# Fox_Sound_Light.net
KiCad netlist of a schematic drawn in EAGLE
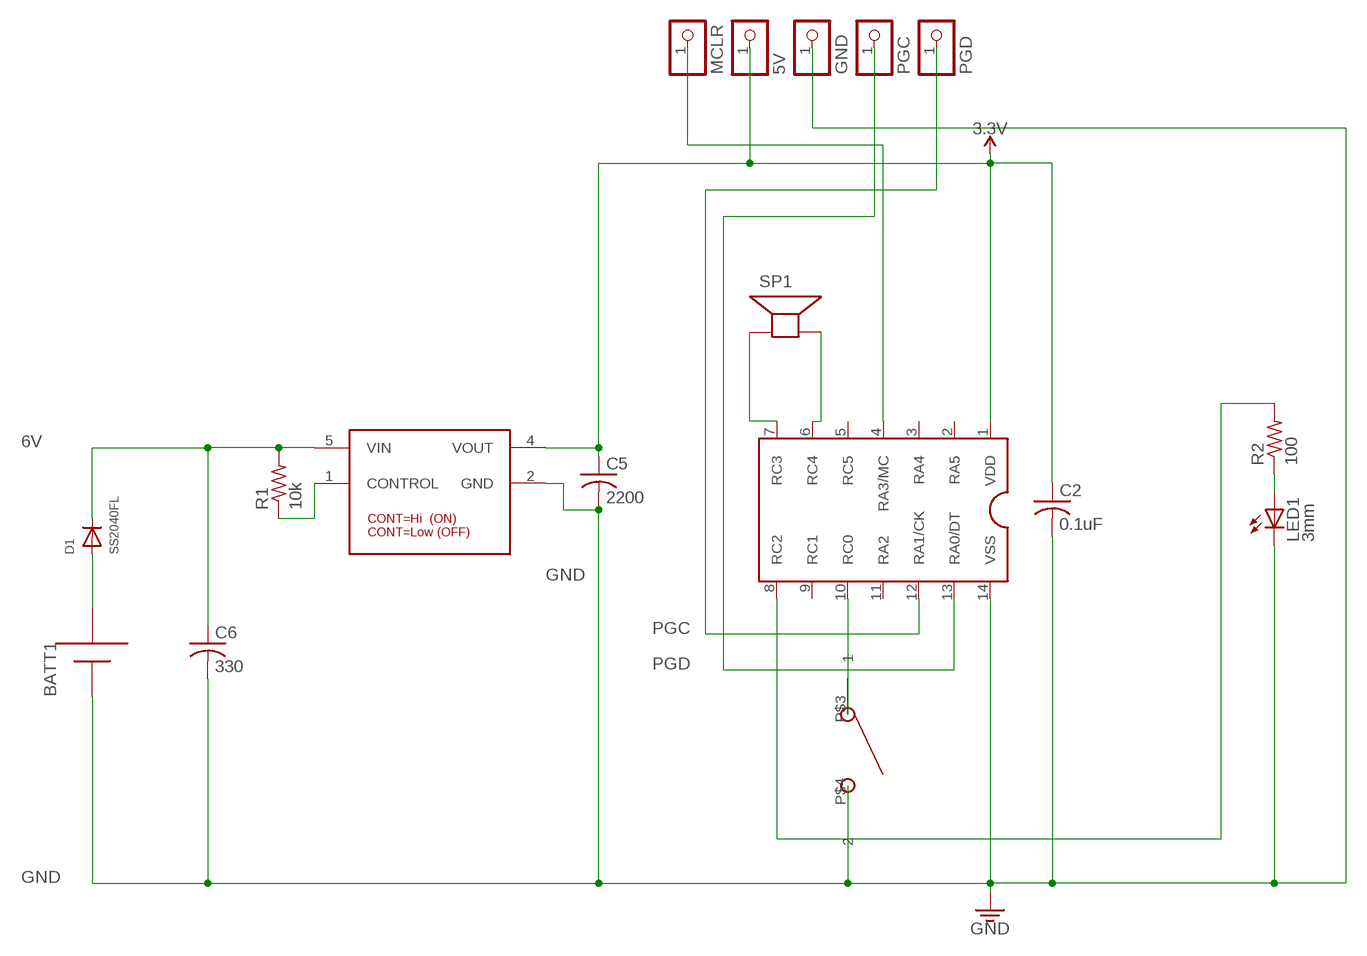
[diagram p0: schematic, sheet 1]

(export (version "E")
  (design (tool "Eeschema 10.0.6"))
  (components
    (comp (ref "BATT1")
      (value "AAA_CR2032X2")
      (footprint "eagle-import:CR2032X2")
      (libsource (lib "eagle-import") (part "AAA_CR2032X2"))
    )
    (comp (ref "C2")
      (value "0.1uF")
      (footprint "eagle-import:C0603")
      (libsource (lib "eagle-import") (part "mathrax_C-USC0603"))
    )
    (comp (ref "C5")
      (value "2200")
      (footprint "eagle-import:C3216")
      (libsource (lib "eagle-import") (part "C-USC3216"))
    )
    (comp (ref "C6")
      (value "330")
      (footprint "eagle-import:C0603")
      (libsource (lib "eagle-import") (part "mathrax_C-USC0603"))
    )
    (comp (ref "D1")
      (value "SS2040FL")
      (footprint "eagle-import:SOD-123FL")
      (libsource (lib "eagle-import") (part "DIODE_SOD-123FL"))
    )
    (comp (ref "JP1")
      (value "MCLR")
      (footprint "eagle-import:1X01-CLEANBIG")
      (libsource (lib "eagle-import") (part "PINHD-1X1CB"))
    )
    (comp (ref "JP2")
      (value "5V")
      (footprint "eagle-import:1X01-CLEANBIG")
      (libsource (lib "eagle-import") (part "PINHD-1X1CB"))
    )
    (comp (ref "JP3")
      (value "GND")
      (footprint "eagle-import:1X01-CLEANBIG")
      (libsource (lib "eagle-import") (part "PINHD-1X1CB"))
    )
    (comp (ref "JP4")
      (value "PGC")
      (footprint "eagle-import:1X01-CLEANBIG")
      (libsource (lib "eagle-import") (part "PINHD-1X1CB"))
    )
    (comp (ref "JP5")
      (value "PGD")
      (footprint "eagle-import:1X01-CLEANBIG")
      (libsource (lib "eagle-import") (part "PINHD-1X1CB"))
    )
    (comp (ref "LED1")
      (value "3mm")
      (footprint "eagle-import:LED3MM")
      (libsource (lib "eagle-import") (part "LED3MM"))
    )
    (comp (ref "NJM2884")
      (value "NJM2884")
      (footprint "eagle-import:NJM2884U1-33")
      (libsource (lib "eagle-import") (part "I-10673_NJM2884U1-33"))
    )
    (comp (ref "R1")
      (value "10k")
      (footprint "eagle-import:R0603")
      (libsource (lib "eagle-import") (part "R-US_R0603"))
    )
    (comp (ref "R2")
      (value "100")
      (footprint "eagle-import:R0603")
      (libsource (lib "eagle-import") (part "R-US_R0603"))
    )
    (comp (ref "SP1")
      (value "SPEAKER_MURATA")
      (footprint "eagle-import:MURATA_PIEZO")
      (libsource (lib "eagle-import") (part "SPEAKER_MURATA"))
    )
    (comp (ref "U$1")
      (value "LEAD-SWITCH_TILT")
      (footprint "eagle-import:TILT-SWITCH")
      (libsource (lib "eagle-import") (part "LEAD-SWITCH_TILT"))
    )
    (comp (ref "U$2")
      (value "PIC16F1705SOP")
      (footprint "eagle-import:14PIN_SOP")
      (libsource (lib "eagle-import") (part "PIC16F1705SOP"))
    )
  )
  (nets
    (net (code "1") (name "/6V") (class "Default")
      (node (ref "C6") (pin "1") (pinfunction "1_1") (pintype "passive"))
      (node (ref "D1") (pin "C") (pinfunction "C_C") (pintype "passive"))
      (node (ref "NJM2884") (pin "5") (pinfunction "VIN_5") (pintype "bidirectional"))
      (node (ref "R1") (pin "2") (pinfunction "2_2") (pintype "passive"))
    )
    (net (code "2") (name "/PGC") (class "Default")
      (node (ref "JP5") (pin "1") (pinfunction "1_1") (pintype "passive"))
      (node (ref "U$2") (pin "12") (pinfunction "RA1/CK_12") (pintype "bidirectional"))
    )
    (net (code "3") (name "/PGD") (class "Default")
      (node (ref "JP4") (pin "1") (pinfunction "1_1") (pintype "passive"))
      (node (ref "U$2") (pin "13") (pinfunction "RA0/DT_13") (pintype "bidirectional"))
    )
    (net (code "4") (name "3.3V") (class "Default")
      (node (ref "C2") (pin "1") (pinfunction "1_1") (pintype "passive"))
      (node (ref "C5") (pin "1") (pinfunction "1_1") (pintype "passive"))
      (node (ref "JP2") (pin "1") (pinfunction "1_1") (pintype "passive"))
      (node (ref "NJM2884") (pin "4") (pinfunction "VOUT_4") (pintype "bidirectional"))
      (node (ref "U$2") (pin "1") (pinfunction "VDD_1") (pintype "bidirectional"))
    )
    (net (code "5") (name "GND") (class "Default")
      (node (ref "BATT1") (pin "GND") (pinfunction "-_GND") (pintype "bidirectional"))
      (node (ref "C2") (pin "2") (pinfunction "2_2") (pintype "passive"))
      (node (ref "C5") (pin "2") (pinfunction "2_2") (pintype "passive"))
      (node (ref "C6") (pin "2") (pinfunction "2_2") (pintype "passive"))
      (node (ref "JP3") (pin "1") (pinfunction "1_1") (pintype "passive"))
      (node (ref "LED1") (pin "K") (pinfunction "C_K") (pintype "passive"))
      (node (ref "NJM2884") (pin "2") (pinfunction "GND_2") (pintype "bidirectional"))
      (node (ref "U$1") (pin "P$4") (pinfunction "2_P$4") (pintype "bidirectional"))
      (node (ref "U$2") (pin "14") (pinfunction "VSS_14") (pintype "bidirectional"))
    )
    (net (code "6") (name "Net-(BATT1-+)") (class "Default")
      (node (ref "BATT1") (pin "V") (pinfunction "+_V") (pintype "bidirectional"))
      (node (ref "D1") (pin "A") (pinfunction "A_A") (pintype "passive"))
    )
    (net (code "7") (name "Net-(LED1-PadA)") (class "Default")
      (node (ref "LED1") (pin "A") (pinfunction "A_A") (pintype "passive"))
      (node (ref "R2") (pin "1") (pinfunction "1_1") (pintype "passive"))
    )
    (net (code "8") (name "Net-(NJM2884-CONTROL)") (class "Default")
      (node (ref "NJM2884") (pin "1") (pinfunction "CONTROL_1") (pintype "bidirectional"))
      (node (ref "R1") (pin "1") (pinfunction "1_1") (pintype "passive"))
    )
    (net (code "9") (name "Net-(SP1-+)") (class "Default")
      (node (ref "SP1") (pin "1") (pinfunction "+_1") (pintype "passive"))
      (node (ref "U$2") (pin "7") (pinfunction "RC3_7") (pintype "bidirectional"))
    )
    (net (code "10") (name "Net-(SP1--)") (class "Default")
      (node (ref "SP1") (pin "2") (pinfunction "-_2") (pintype "passive"))
      (node (ref "U$2") (pin "6") (pinfunction "RC4_6") (pintype "bidirectional"))
    )
    (net (code "11") (name "Net-(U$1-1)") (class "Default")
      (node (ref "U$1") (pin "P$3") (pinfunction "1_P$3") (pintype "bidirectional"))
      (node (ref "U$2") (pin "10") (pinfunction "RC0_10") (pintype "bidirectional"))
    )
    (net (code "12") (name "Net-(U$2-RA3{slash}MC)") (class "Default")
      (node (ref "JP1") (pin "1") (pinfunction "1_1") (pintype "passive"))
      (node (ref "U$2") (pin "4") (pinfunction "RA3/MC_4") (pintype "bidirectional"))
    )
    (net (code "13") (name "Net-(U$2-RC2)") (class "Default")
      (node (ref "R2") (pin "2") (pinfunction "2_2") (pintype "passive"))
      (node (ref "U$2") (pin "8") (pinfunction "RC2_8") (pintype "bidirectional"))
    )
    (net (code "14") (name "unconnected-(U$2-RA2-Pad11)") (class "Default")
      (node (ref "U$2") (pin "11") (pinfunction "RA2_11") (pintype "bidirectional"))
    )
    (net (code "15") (name "unconnected-(U$2-RA4-Pad3)") (class "Default")
      (node (ref "U$2") (pin "3") (pinfunction "RA4_3") (pintype "bidirectional"))
    )
    (net (code "16") (name "unconnected-(U$2-RA5-Pad2)") (class "Default")
      (node (ref "U$2") (pin "2") (pinfunction "RA5_2") (pintype "bidirectional"))
    )
    (net (code "17") (name "unconnected-(U$2-RC1-Pad9)") (class "Default")
      (node (ref "U$2") (pin "9") (pinfunction "RC1_9") (pintype "bidirectional"))
    )
    (net (code "18") (name "unconnected-(U$2-RC5-Pad5)") (class "Default")
      (node (ref "U$2") (pin "5") (pinfunction "RC5_5") (pintype "bidirectional"))
    )
  )
)
